# midiprog.net
KiCad netlist of a schematic drawn in EAGLE
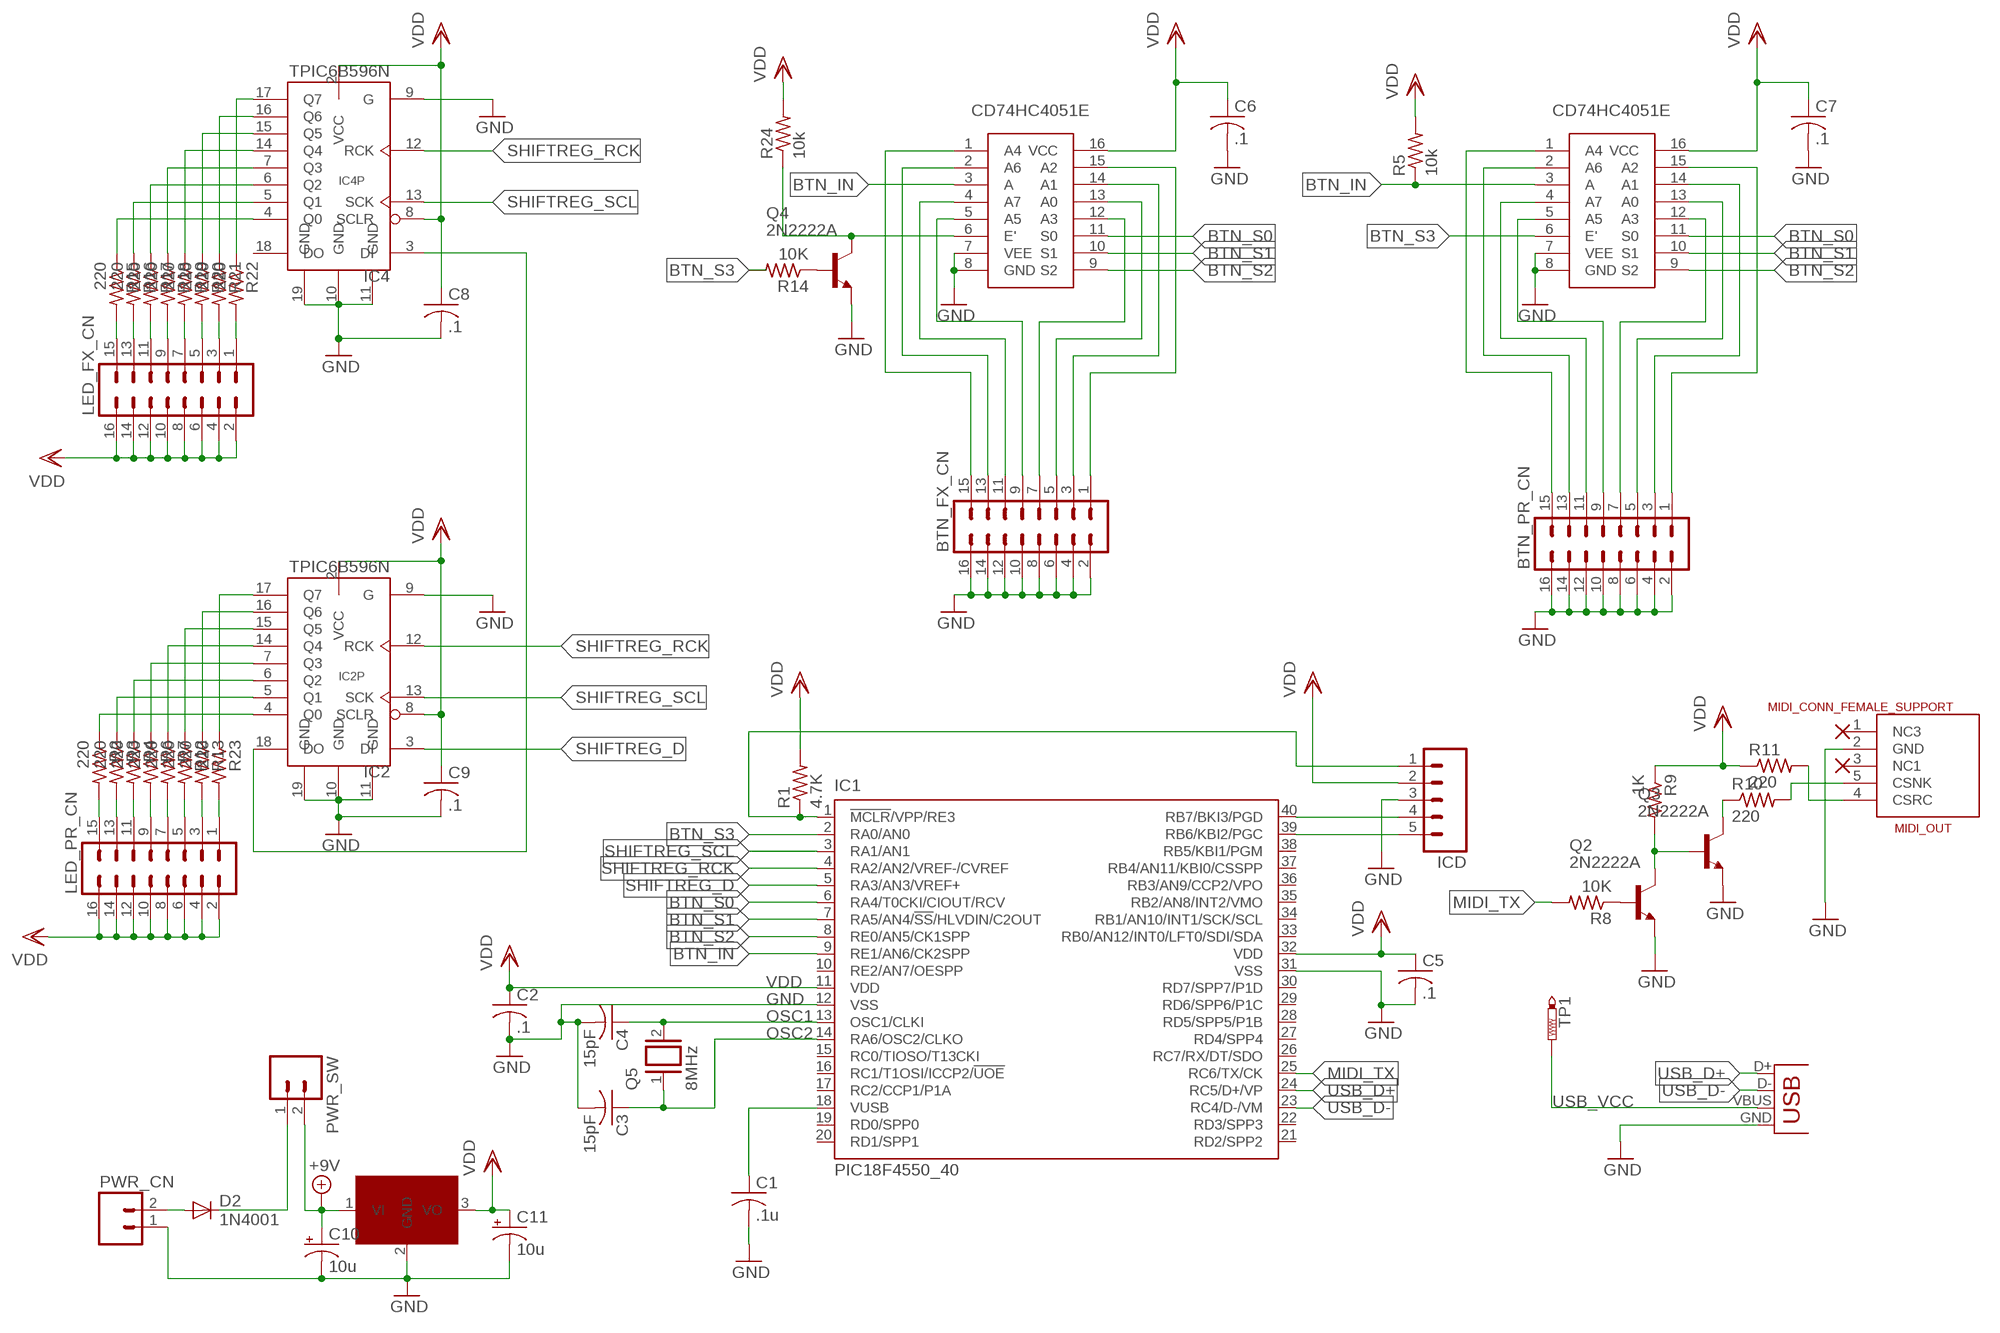
[diagram p0: schematic, sheet 1]

(export (version "E")
  (design (tool "Eeschema 10.0.6"))
  (components
    (comp (ref "BTN_FX_CN")
      (value "MA08-2")
      (footprint "eagle-import:MA08-2")
      (libsource (lib "eagle-import") (part "MA08-2"))
    )
    (comp (ref "BTN_PR_CN")
      (value "MA08-2")
      (footprint "eagle-import:MA08-2")
      (libsource (lib "eagle-import") (part "MA08-2"))
    )
    (comp (ref "C1")
      (value ".1u")
      (footprint "eagle-import:C050-025X075")
      (libsource (lib "eagle-import") (part "C-US050-025X075"))
    )
    (comp (ref "C2")
      (value ".1")
      (footprint "eagle-import:C050-025X075")
      (libsource (lib "eagle-import") (part "C-US050-025X075"))
    )
    (comp (ref "C3")
      (value "15pF")
      (footprint "eagle-import:C050-025X075")
      (libsource (lib "eagle-import") (part "C-US050-025X075"))
    )
    (comp (ref "C4")
      (value "15pF")
      (footprint "eagle-import:C050-025X075")
      (libsource (lib "eagle-import") (part "C-US050-025X075"))
    )
    (comp (ref "C5")
      (value ".1")
      (footprint "eagle-import:C050-025X075")
      (libsource (lib "eagle-import") (part "C-US050-025X075"))
    )
    (comp (ref "C6")
      (value ".1")
      (footprint "eagle-import:C050-025X075")
      (libsource (lib "eagle-import") (part "C-US050-025X075"))
    )
    (comp (ref "C7")
      (value ".1")
      (footprint "eagle-import:C050-025X075")
      (libsource (lib "eagle-import") (part "C-US050-025X075"))
    )
    (comp (ref "C8")
      (value ".1")
      (footprint "eagle-import:C050-025X075")
      (libsource (lib "eagle-import") (part "C-US050-025X075"))
    )
    (comp (ref "C9")
      (value ".1")
      (footprint "eagle-import:C050-025X075")
      (libsource (lib "eagle-import") (part "C-US050-025X075"))
    )
    (comp (ref "C10")
      (value "10u")
      (footprint "eagle-import:E2,5-6")
      (libsource (lib "eagle-import") (part "CPOL-USE2.5-6"))
    )
    (comp (ref "C11")
      (value "10u")
      (footprint "eagle-import:E2,5-6")
      (libsource (lib "eagle-import") (part "CPOL-USE2.5-6"))
    )
    (comp (ref "D2")
      (value "1N4001")
      (footprint "eagle-import:DO41-10")
      (libsource (lib "eagle-import") (part "1N4004"))
    )
    (comp (ref "IC1")
      (value "PIC18F4550_40")
      (footprint "eagle-import:DIL40")
      (fields (field (name "MF") "MICROCHIP") (field (name "MPN") "PIC18F4550-I/P"))
      (libsource (lib "eagle-import") (part "PIC18F4_40550"))
    )
    (comp (ref "IC2")
      (value "TPIC6B596N")
      (footprint "eagle-import:DIL20")
      (libsource (lib "eagle-import") (part "TPIC6B596N"))
    )
    (comp (ref "IC4")
      (value "TPIC6B596N")
      (footprint "eagle-import:DIL20")
      (libsource (lib "eagle-import") (part "TPIC6B596N"))
    )
    (comp (ref "ICD")
      (value "MA05")
      (footprint "eagle-import:05PA")
      (libsource (lib "eagle-import") (part "MA05"))
    )
    (comp (ref "JP1")
      (value "USB-B")
      (footprint "eagle-import:USB-B-PTH")
      (libsource (lib "eagle-import") (part "USBPTH"))
    )
    (comp (ref "LED_FX_CN")
      (value "MA08-2")
      (footprint "eagle-import:MA08-2")
      (libsource (lib "eagle-import") (part "MA08-2"))
    )
    (comp (ref "LED_PR_CN")
      (value "MA08-2")
      (footprint "eagle-import:MA08-2")
      (libsource (lib "eagle-import") (part "MA08-2"))
    )
    (comp (ref "MIDI_OUT")
      (value "MIDI_CONN_FEMALE_SUPPORT")
      (footprint "eagle-import:DIN_5_FEMALE_SUPPORT")
      (libsource (lib "eagle-import") (part "MIDI_CONN_FEMALE_SUPPORT"))
    )
    (comp (ref "PWR_CN")
      (value "M02")
      (footprint "eagle-import:02P")
      (libsource (lib "eagle-import") (part "M02"))
    )
    (comp (ref "PWR_SW")
      (value "M02")
      (footprint "eagle-import:02P")
      (libsource (lib "eagle-import") (part "M02"))
    )
    (comp (ref "Q2")
      (value "2N2222A")
      (footprint "eagle-import:TO18")
      (libsource (lib "eagle-import") (part "2N2222A"))
    )
    (comp (ref "Q3")
      (value "2N2222A")
      (footprint "eagle-import:TO18")
      (libsource (lib "eagle-import") (part "2N2222A"))
    )
    (comp (ref "Q4")
      (value "2N2222A")
      (footprint "eagle-import:TO18")
      (libsource (lib "eagle-import") (part "2N2222A"))
    )
    (comp (ref "Q5")
      (value "8MHz")
      (footprint "eagle-import:QS")
      (libsource (lib "eagle-import") (part "XTAL/S"))
    )
    (comp (ref "R1")
      (value "4.7K")
      (footprint "eagle-import:0207_10")
      (libsource (lib "eagle-import") (part "R-US_0207/10"))
    )
    (comp (ref "R2")
      (value "220")
      (footprint "eagle-import:0207_10")
      (libsource (lib "eagle-import") (part "R-US_0207/10"))
    )
    (comp (ref "R3")
      (value "220")
      (footprint "eagle-import:0207_10")
      (libsource (lib "eagle-import") (part "R-US_0207/10"))
    )
    (comp (ref "R4")
      (value "220")
      (footprint "eagle-import:0207_10")
      (libsource (lib "eagle-import") (part "R-US_0207/10"))
    )
    (comp (ref "R5")
      (value "10k")
      (footprint "eagle-import:0207_10")
      (libsource (lib "eagle-import") (part "R-US_0207/10"))
    )
    (comp (ref "R6")
      (value "220")
      (footprint "eagle-import:0207_10")
      (libsource (lib "eagle-import") (part "R-US_0207/10"))
    )
    (comp (ref "R7")
      (value "220")
      (footprint "eagle-import:0207_10")
      (libsource (lib "eagle-import") (part "R-US_0207/10"))
    )
    (comp (ref "R8")
      (value "10K")
      (footprint "eagle-import:0207_10")
      (libsource (lib "eagle-import") (part "R-US_0207/10"))
    )
    (comp (ref "R9")
      (value "1K")
      (footprint "eagle-import:0207_10")
      (libsource (lib "eagle-import") (part "R-US_0207/10"))
    )
    (comp (ref "R10")
      (value "220")
      (footprint "eagle-import:0207_10")
      (libsource (lib "eagle-import") (part "R-US_0207/10"))
    )
    (comp (ref "R11")
      (value "220")
      (footprint "eagle-import:0207_10")
      (libsource (lib "eagle-import") (part "R-US_0207/10"))
    )
    (comp (ref "R12")
      (value "220")
      (footprint "eagle-import:0207_10")
      (libsource (lib "eagle-import") (part "R-US_0207/10"))
    )
    (comp (ref "R13")
      (value "220")
      (footprint "eagle-import:0207_10")
      (libsource (lib "eagle-import") (part "R-US_0207/10"))
    )
    (comp (ref "R14")
      (value "10K")
      (footprint "eagle-import:0207_10")
      (libsource (lib "eagle-import") (part "R-US_0207/10"))
    )
    (comp (ref "R15")
      (value "220")
      (footprint "eagle-import:0207_10")
      (libsource (lib "eagle-import") (part "R-US_0207/10"))
    )
    (comp (ref "R16")
      (value "220")
      (footprint "eagle-import:0207_10")
      (libsource (lib "eagle-import") (part "R-US_0207/10"))
    )
    (comp (ref "R17")
      (value "220")
      (footprint "eagle-import:0207_10")
      (libsource (lib "eagle-import") (part "R-US_0207/10"))
    )
    (comp (ref "R18")
      (value "220")
      (footprint "eagle-import:0207_10")
      (libsource (lib "eagle-import") (part "R-US_0207/10"))
    )
    (comp (ref "R19")
      (value "220")
      (footprint "eagle-import:0207_10")
      (libsource (lib "eagle-import") (part "R-US_0207/10"))
    )
    (comp (ref "R20")
      (value "220")
      (footprint "eagle-import:0207_10")
      (libsource (lib "eagle-import") (part "R-US_0207/10"))
    )
    (comp (ref "R21")
      (value "220")
      (footprint "eagle-import:0207_10")
      (libsource (lib "eagle-import") (part "R-US_0207/10"))
    )
    (comp (ref "R22")
      (value "220")
      (footprint "eagle-import:0207_10")
      (libsource (lib "eagle-import") (part "R-US_0207/10"))
    )
    (comp (ref "R23")
      (value "220")
      (footprint "eagle-import:0207_10")
      (libsource (lib "eagle-import") (part "R-US_0207/10"))
    )
    (comp (ref "R24")
      (value "10k")
      (footprint "eagle-import:0207_10")
      (libsource (lib "eagle-import") (part "R-US_0207/10"))
    )
    (comp (ref "TP1")
      (value "PTR1PAD1-17")
      (footprint "eagle-import:P1-17")
      (libsource (lib "eagle-import") (part "PTR1PAD1-17"))
    )
    (comp (ref "U$1")
      (value "CD74HC4051E")
      (footprint "eagle-import:CD74HC4051E")
      (libsource (lib "eagle-import") (part "CD74HC4051E"))
    )
    (comp (ref "U$2")
      (value "CD74HC4051E")
      (footprint "eagle-import:CD74HC4051E")
      (libsource (lib "eagle-import") (part "CD74HC4051E"))
    )
    (comp (ref "U$3")
      (value "7805")
      (footprint "eagle-import:JKDFJD")
      (libsource (lib "eagle-import") (part "7805"))
    )
  )
  (nets
    (net (code "1") (name "+9V") (class "Default")
      (node (ref "C10") (pin "+") (pinfunction "+_+") (pintype "passive"))
      (node (ref "PWR_SW") (pin "2") (pinfunction "2_2") (pintype "passive"))
      (node (ref "U$3") (pin "1") (pinfunction "VI_1") (pintype "bidirectional"))
    )
    (net (code "2") (name "/OSC1") (class "Default")
      (node (ref "C4") (pin "1") (pinfunction "1_1") (pintype "passive"))
      (node (ref "IC1") (pin "13") (pinfunction "OSC1/CLKI_13") (pintype "input"))
      (node (ref "Q5") (pin "2") (pinfunction "2_2") (pintype "passive"))
    )
    (net (code "3") (name "/OSC2") (class "Default")
      (node (ref "C3") (pin "1") (pinfunction "1_1") (pintype "passive"))
      (node (ref "IC1") (pin "14") (pinfunction "RA6/OSC2/CLKO_14") (pintype "output"))
      (node (ref "Q5") (pin "1") (pinfunction "1_1") (pintype "passive"))
    )
    (net (code "4") (name "/USB_VCC") (class "Default")
      (node (ref "JP1") (pin "VBUS") (pinfunction "VBUS_VBUS") (pintype "bidirectional"))
      (node (ref "TP1") (pin "TP") (pinfunction "TP_TP") (pintype "input"))
    )
    (net (code "5") (name "BTN_IN") (class "Default")
      (node (ref "IC1") (pin "9") (pinfunction "RE1/AN6/CK2SPP_9") (pintype "bidirectional"))
      (node (ref "R5") (pin "1") (pinfunction "1_1") (pintype "passive"))
      (node (ref "U$1") (pin "3") (pinfunction "A_3") (pintype "bidirectional"))
      (node (ref "U$2") (pin "3") (pinfunction "A_3") (pintype "bidirectional"))
    )
    (net (code "6") (name "BTN_S0") (class "Default")
      (node (ref "IC1") (pin "6") (pinfunction "RA4/T0CKI/CIOUT/RCV_6") (pintype "bidirectional"))
      (node (ref "U$1") (pin "11") (pinfunction "S0_11") (pintype "bidirectional"))
      (node (ref "U$2") (pin "11") (pinfunction "S0_11") (pintype "bidirectional"))
    )
    (net (code "7") (name "BTN_S1") (class "Default")
      (node (ref "IC1") (pin "7") (pinfunction "RA5/AN4/~{SS}/HLVDIN/C2OUT_7") (pintype "bidirectional"))
      (node (ref "U$1") (pin "10") (pinfunction "S1_10") (pintype "bidirectional"))
      (node (ref "U$2") (pin "10") (pinfunction "S1_10") (pintype "bidirectional"))
    )
    (net (code "8") (name "BTN_S2") (class "Default")
      (node (ref "IC1") (pin "8") (pinfunction "RE0/AN5/CK1SPP_8") (pintype "bidirectional"))
      (node (ref "U$1") (pin "9") (pinfunction "S2_9") (pintype "bidirectional"))
      (node (ref "U$2") (pin "9") (pinfunction "S2_9") (pintype "bidirectional"))
    )
    (net (code "9") (name "BTN_S3") (class "Default")
      (node (ref "IC1") (pin "2") (pinfunction "RA0/AN0_2") (pintype "bidirectional"))
      (node (ref "R14") (pin "2") (pinfunction "2_2") (pintype "passive"))
      (node (ref "U$1") (pin "6") (pinfunction "E'_6") (pintype "bidirectional"))
    )
    (net (code "10") (name "GND") (class "Default")
      (node (ref "BTN_FX_CN") (pin "10") (pinfunction "10_10") (pintype "passive"))
      (node (ref "BTN_FX_CN") (pin "12") (pinfunction "12_12") (pintype "passive"))
      (node (ref "BTN_FX_CN") (pin "14") (pinfunction "14_14") (pintype "passive"))
      (node (ref "BTN_FX_CN") (pin "16") (pinfunction "16_16") (pintype "passive"))
      (node (ref "BTN_FX_CN") (pin "2") (pinfunction "2_2") (pintype "passive"))
      (node (ref "BTN_FX_CN") (pin "4") (pinfunction "4_4") (pintype "passive"))
      (node (ref "BTN_FX_CN") (pin "6") (pinfunction "6_6") (pintype "passive"))
      (node (ref "BTN_FX_CN") (pin "8") (pinfunction "8_8") (pintype "passive"))
      (node (ref "BTN_PR_CN") (pin "10") (pinfunction "10_10") (pintype "passive"))
      (node (ref "BTN_PR_CN") (pin "12") (pinfunction "12_12") (pintype "passive"))
      (node (ref "BTN_PR_CN") (pin "14") (pinfunction "14_14") (pintype "passive"))
      (node (ref "BTN_PR_CN") (pin "16") (pinfunction "16_16") (pintype "passive"))
      (node (ref "BTN_PR_CN") (pin "2") (pinfunction "2_2") (pintype "passive"))
      (node (ref "BTN_PR_CN") (pin "4") (pinfunction "4_4") (pintype "passive"))
      (node (ref "BTN_PR_CN") (pin "6") (pinfunction "6_6") (pintype "passive"))
      (node (ref "BTN_PR_CN") (pin "8") (pinfunction "8_8") (pintype "passive"))
      (node (ref "C1") (pin "2") (pinfunction "2_2") (pintype "passive"))
      (node (ref "C10") (pin "-") (pinfunction "-_-") (pintype "passive"))
      (node (ref "C11") (pin "-") (pinfunction "-_-") (pintype "passive"))
      (node (ref "C2") (pin "2") (pinfunction "2_2") (pintype "passive"))
      (node (ref "C3") (pin "2") (pinfunction "2_2") (pintype "passive"))
      (node (ref "C4") (pin "2") (pinfunction "2_2") (pintype "passive"))
      (node (ref "C5") (pin "2") (pinfunction "2_2") (pintype "passive"))
      (node (ref "C6") (pin "2") (pinfunction "2_2") (pintype "passive"))
      (node (ref "C7") (pin "2") (pinfunction "2_2") (pintype "passive"))
      (node (ref "C8") (pin "2") (pinfunction "2_2") (pintype "passive"))
      (node (ref "C9") (pin "2") (pinfunction "2_2") (pintype "passive"))
      (node (ref "IC1") (pin "12") (pinfunction "VSS_12") (pintype "power_in"))
      (node (ref "IC1") (pin "31") (pinfunction "VSS_31") (pintype "power_in"))
      (node (ref "IC2") (pin "10") (pinfunction "GND_10") (pintype "power_in"))
      (node (ref "IC2") (pin "11") (pinfunction "GND_11") (pintype "power_in"))
      (node (ref "IC2") (pin "19") (pinfunction "GND_19") (pintype "power_in"))
      (node (ref "IC2") (pin "9") (pinfunction "G_9") (pintype "input"))
      (node (ref "IC4") (pin "10") (pinfunction "GND_10") (pintype "power_in"))
      (node (ref "IC4") (pin "11") (pinfunction "GND_11") (pintype "power_in"))
      (node (ref "IC4") (pin "19") (pinfunction "GND_19") (pintype "power_in"))
      (node (ref "IC4") (pin "9") (pinfunction "G_9") (pintype "input"))
      (node (ref "ICD") (pin "3") (pinfunction "3_3") (pintype "passive"))
      (node (ref "JP1") (pin "GND") (pinfunction "GND_GND") (pintype "bidirectional"))
      (node (ref "MIDI_OUT") (pin "2") (pinfunction "GND_2") (pintype "bidirectional"))
      (node (ref "PWR_CN") (pin "1") (pinfunction "1_1") (pintype "passive"))
      (node (ref "Q2") (pin "1") (pinfunction "E_1") (pintype "passive"))
      (node (ref "Q3") (pin "1") (pinfunction "E_1") (pintype "passive"))
      (node (ref "Q4") (pin "1") (pinfunction "E_1") (pintype "passive"))
      (node (ref "U$1") (pin "7") (pinfunction "VEE_7") (pintype "bidirectional"))
      (node (ref "U$1") (pin "8") (pinfunction "GND_8") (pintype "bidirectional"))
      (node (ref "U$2") (pin "7") (pinfunction "VEE_7") (pintype "bidirectional"))
      (node (ref "U$2") (pin "8") (pinfunction "GND_8") (pintype "bidirectional"))
      (node (ref "U$3") (pin "2") (pinfunction "GND_2") (pintype "bidirectional"))
    )
    (net (code "11") (name "MIDI_TX") (class "Default")
      (node (ref "IC1") (pin "25") (pinfunction "RC6/TX/CK_25") (pintype "bidirectional"))
      (node (ref "R8") (pin "2") (pinfunction "2_2") (pintype "passive"))
    )
    (net (code "12") (name "Net-(D2-PadA)") (class "Default")
      (node (ref "D2") (pin "A") (pinfunction "A_A") (pintype "passive"))
      (node (ref "PWR_CN") (pin "2") (pinfunction "2_2") (pintype "passive"))
    )
    (net (code "13") (name "Net-(D2-PadC)") (class "Default")
      (node (ref "D2") (pin "C") (pinfunction "C_C") (pintype "passive"))
      (node (ref "PWR_SW") (pin "1") (pinfunction "1_1") (pintype "passive"))
    )
    (net (code "14") (name "Net-(IC1-RB6{slash}KBI2{slash}PGC)") (class "Default")
      (node (ref "IC1") (pin "39") (pinfunction "RB6/KBI2/PGC_39") (pintype "bidirectional"))
      (node (ref "ICD") (pin "5") (pinfunction "5_5") (pintype "passive"))
    )
    (net (code "15") (name "Net-(IC1-RB7{slash}BKI3{slash}PGD)") (class "Default")
      (node (ref "IC1") (pin "40") (pinfunction "RB7/BKI3/PGD_40") (pintype "bidirectional"))
      (node (ref "ICD") (pin "4") (pinfunction "4_4") (pintype "passive"))
    )
    (net (code "16") (name "Net-(IC1-VUSB)") (class "Default")
      (node (ref "C1") (pin "1") (pinfunction "1_1") (pintype "passive"))
      (node (ref "IC1") (pin "18") (pinfunction "VUSB_18") (pintype "bidirectional"))
    )
    (net (code "17") (name "Net-(IC1-~{MCLR}{slash}VPP{slash}RE3)") (class "Default")
      (node (ref "IC1") (pin "1") (pinfunction "~{MCLR}/VPP/RE3_1") (pintype "input"))
      (node (ref "ICD") (pin "1") (pinfunction "1_1") (pintype "passive"))
      (node (ref "R1") (pin "1") (pinfunction "1_1") (pintype "passive"))
    )
    (net (code "18") (name "Net-(IC2A-DO)") (class "Default")
      (node (ref "IC2") (pin "18") (pinfunction "DO_18") (pintype "output"))
      (node (ref "IC4") (pin "3") (pinfunction "DI_3") (pintype "input"))
    )
    (net (code "19") (name "Net-(IC2A-Q0)") (class "Default")
      (node (ref "IC2") (pin "4") (pinfunction "Q0_4") (pintype "open_collector"))
      (node (ref "R2") (pin "1") (pinfunction "1_1") (pintype "passive"))
    )
    (net (code "20") (name "Net-(IC2A-Q1)") (class "Default")
      (node (ref "IC2") (pin "5") (pinfunction "Q1_5") (pintype "open_collector"))
      (node (ref "R3") (pin "1") (pinfunction "1_1") (pintype "passive"))
    )
    (net (code "21") (name "Net-(IC2A-Q2)") (class "Default")
      (node (ref "IC2") (pin "6") (pinfunction "Q2_6") (pintype "open_collector"))
      (node (ref "R4") (pin "1") (pinfunction "1_1") (pintype "passive"))
    )
    (net (code "22") (name "Net-(IC2A-Q3)") (class "Default")
      (node (ref "IC2") (pin "7") (pinfunction "Q3_7") (pintype "open_collector"))
      (node (ref "R6") (pin "1") (pinfunction "1_1") (pintype "passive"))
    )
    (net (code "23") (name "Net-(IC2A-Q4)") (class "Default")
      (node (ref "IC2") (pin "14") (pinfunction "Q4_14") (pintype "open_collector"))
      (node (ref "R7") (pin "1") (pinfunction "1_1") (pintype "passive"))
    )
    (net (code "24") (name "Net-(IC2A-Q5)") (class "Default")
      (node (ref "IC2") (pin "15") (pinfunction "Q5_15") (pintype "open_collector"))
      (node (ref "R12") (pin "1") (pinfunction "1_1") (pintype "passive"))
    )
    (net (code "25") (name "Net-(IC2A-Q6)") (class "Default")
      (node (ref "IC2") (pin "16") (pinfunction "Q6_16") (pintype "open_collector"))
      (node (ref "R13") (pin "1") (pinfunction "1_1") (pintype "passive"))
    )
    (net (code "26") (name "Net-(IC2A-Q7)") (class "Default")
      (node (ref "IC2") (pin "17") (pinfunction "Q7_17") (pintype "open_collector"))
      (node (ref "R23") (pin "1") (pinfunction "1_1") (pintype "passive"))
    )
    (net (code "27") (name "Net-(IC4A-Q0)") (class "Default")
      (node (ref "IC4") (pin "4") (pinfunction "Q0_4") (pintype "open_collector"))
      (node (ref "R15") (pin "1") (pinfunction "1_1") (pintype "passive"))
    )
    (net (code "28") (name "Net-(IC4A-Q1)") (class "Default")
      (node (ref "IC4") (pin "5") (pinfunction "Q1_5") (pintype "open_collector"))
      (node (ref "R16") (pin "1") (pinfunction "1_1") (pintype "passive"))
    )
    (net (code "29") (name "Net-(IC4A-Q2)") (class "Default")
      (node (ref "IC4") (pin "6") (pinfunction "Q2_6") (pintype "open_collector"))
      (node (ref "R17") (pin "1") (pinfunction "1_1") (pintype "passive"))
    )
    (net (code "30") (name "Net-(IC4A-Q3)") (class "Default")
      (node (ref "IC4") (pin "7") (pinfunction "Q3_7") (pintype "open_collector"))
      (node (ref "R18") (pin "1") (pinfunction "1_1") (pintype "passive"))
    )
    (net (code "31") (name "Net-(IC4A-Q4)") (class "Default")
      (node (ref "IC4") (pin "14") (pinfunction "Q4_14") (pintype "open_collector"))
      (node (ref "R19") (pin "1") (pinfunction "1_1") (pintype "passive"))
    )
    (net (code "32") (name "Net-(IC4A-Q5)") (class "Default")
      (node (ref "IC4") (pin "15") (pinfunction "Q5_15") (pintype "open_collector"))
      (node (ref "R20") (pin "1") (pinfunction "1_1") (pintype "passive"))
    )
    (net (code "33") (name "Net-(IC4A-Q6)") (class "Default")
      (node (ref "IC4") (pin "16") (pinfunction "Q6_16") (pintype "open_collector"))
      (node (ref "R21") (pin "1") (pinfunction "1_1") (pintype "passive"))
    )
    (net (code "34") (name "Net-(IC4A-Q7)") (class "Default")
      (node (ref "IC4") (pin "17") (pinfunction "Q7_17") (pintype "open_collector"))
      (node (ref "R22") (pin "1") (pinfunction "1_1") (pintype "passive"))
    )
    (net (code "35") (name "Net-(LED_FX_CN-Pad1)") (class "Default")
      (node (ref "LED_FX_CN") (pin "1") (pinfunction "1_1") (pintype "passive"))
      (node (ref "R22") (pin "2") (pinfunction "2_2") (pintype "passive"))
    )
    (net (code "36") (name "Net-(LED_FX_CN-Pad3)") (class "Default")
      (node (ref "LED_FX_CN") (pin "3") (pinfunction "3_3") (pintype "passive"))
      (node (ref "R21") (pin "2") (pinfunction "2_2") (pintype "passive"))
    )
    (net (code "37") (name "Net-(LED_FX_CN-Pad5)") (class "Default")
      (node (ref "LED_FX_CN") (pin "5") (pinfunction "5_5") (pintype "passive"))
      (node (ref "R20") (pin "2") (pinfunction "2_2") (pintype "passive"))
    )
    (net (code "38") (name "Net-(LED_FX_CN-Pad7)") (class "Default")
      (node (ref "LED_FX_CN") (pin "7") (pinfunction "7_7") (pintype "passive"))
      (node (ref "R19") (pin "2") (pinfunction "2_2") (pintype "passive"))
    )
    (net (code "39") (name "Net-(LED_FX_CN-Pad9)") (class "Default")
      (node (ref "LED_FX_CN") (pin "9") (pinfunction "9_9") (pintype "passive"))
      (node (ref "R18") (pin "2") (pinfunction "2_2") (pintype "passive"))
    )
    (net (code "40") (name "Net-(LED_FX_CN-Pad11)") (class "Default")
      (node (ref "LED_FX_CN") (pin "11") (pinfunction "11_11") (pintype "passive"))
      (node (ref "R17") (pin "2") (pinfunction "2_2") (pintype "passive"))
    )
    (net (code "41") (name "Net-(LED_FX_CN-Pad13)") (class "Default")
      (node (ref "LED_FX_CN") (pin "13") (pinfunction "13_13") (pintype "passive"))
      (node (ref "R16") (pin "2") (pinfunction "2_2") (pintype "passive"))
    )
    (net (code "42") (name "Net-(LED_FX_CN-Pad15)") (class "Default")
      (node (ref "LED_FX_CN") (pin "15") (pinfunction "15_15") (pintype "passive"))
      (node (ref "R15") (pin "2") (pinfunction "2_2") (pintype "passive"))
    )
    (net (code "43") (name "Net-(LED_PR_CN-Pad1)") (class "Default")
      (node (ref "LED_PR_CN") (pin "1") (pinfunction "1_1") (pintype "passive"))
      (node (ref "R23") (pin "2") (pinfunction "2_2") (pintype "passive"))
    )
    (net (code "44") (name "Net-(LED_PR_CN-Pad3)") (class "Default")
      (node (ref "LED_PR_CN") (pin "3") (pinfunction "3_3") (pintype "passive"))
      (node (ref "R13") (pin "2") (pinfunction "2_2") (pintype "passive"))
    )
    (net (code "45") (name "Net-(LED_PR_CN-Pad5)") (class "Default")
      (node (ref "LED_PR_CN") (pin "5") (pinfunction "5_5") (pintype "passive"))
      (node (ref "R12") (pin "2") (pinfunction "2_2") (pintype "passive"))
    )
    (net (code "46") (name "Net-(LED_PR_CN-Pad7)") (class "Default")
      (node (ref "LED_PR_CN") (pin "7") (pinfunction "7_7") (pintype "passive"))
      (node (ref "R7") (pin "2") (pinfunction "2_2") (pintype "passive"))
    )
    (net (code "47") (name "Net-(LED_PR_CN-Pad9)") (class "Default")
      (node (ref "LED_PR_CN") (pin "9") (pinfunction "9_9") (pintype "passive"))
      (node (ref "R6") (pin "2") (pinfunction "2_2") (pintype "passive"))
    )
    (net (code "48") (name "Net-(LED_PR_CN-Pad11)") (class "Default")
      (node (ref "LED_PR_CN") (pin "11") (pinfunction "11_11") (pintype "passive"))
      (node (ref "R4") (pin "2") (pinfunction "2_2") (pintype "passive"))
    )
    (net (code "49") (name "Net-(LED_PR_CN-Pad13)") (class "Default")
      (node (ref "LED_PR_CN") (pin "13") (pinfunction "13_13") (pintype "passive"))
      (node (ref "R3") (pin "2") (pinfunction "2_2") (pintype "passive"))
    )
    (net (code "50") (name "Net-(LED_PR_CN-Pad15)") (class "Default")
      (node (ref "LED_PR_CN") (pin "15") (pinfunction "15_15") (pintype "passive"))
      (node (ref "R2") (pin "2") (pinfunction "2_2") (pintype "passive"))
    )
    (net (code "51") (name "Net-(MIDI_OUT-CSNK)") (class "Default")
      (node (ref "MIDI_OUT") (pin "5") (pinfunction "CSNK_5") (pintype "bidirectional"))
      (node (ref "R10") (pin "2") (pinfunction "2_2") (pintype "passive"))
    )
    (net (code "52") (name "Net-(MIDI_OUT-CSRC)") (class "Default")
      (node (ref "MIDI_OUT") (pin "4") (pinfunction "CSRC_4") (pintype "bidirectional"))
      (node (ref "R11") (pin "2") (pinfunction "2_2") (pintype "passive"))
    )
    (net (code "53") (name "Net-(Q2-B)") (class "Default")
      (node (ref "Q2") (pin "2") (pinfunction "B_2") (pintype "passive"))
      (node (ref "R8") (pin "1") (pinfunction "1_1") (pintype "passive"))
    )
    (net (code "54") (name "Net-(Q2-C)") (class "Default")
      (node (ref "Q2") (pin "3") (pinfunction "C_3") (pintype "passive"))
      (node (ref "Q3") (pin "2") (pinfunction "B_2") (pintype "passive"))
      (node (ref "R9") (pin "2") (pinfunction "2_2") (pintype "passive"))
    )
    (net (code "55") (name "Net-(Q3-C)") (class "Default")
      (node (ref "Q3") (pin "3") (pinfunction "C_3") (pintype "passive"))
      (node (ref "R10") (pin "1") (pinfunction "1_1") (pintype "passive"))
    )
    (net (code "56") (name "Net-(Q4-B)") (class "Default")
      (node (ref "Q4") (pin "2") (pinfunction "B_2") (pintype "passive"))
      (node (ref "R14") (pin "1") (pinfunction "1_1") (pintype "passive"))
    )
    (net (code "57") (name "Net-(Q4-C)") (class "Default")
      (node (ref "Q4") (pin "3") (pinfunction "C_3") (pintype "passive"))
      (node (ref "R24") (pin "1") (pinfunction "1_1") (pintype "passive"))
      (node (ref "U$2") (pin "6") (pinfunction "E'_6") (pintype "bidirectional"))
    )
    (net (code "58") (name "Net-(U$1-A0)") (class "Default")
      (node (ref "BTN_PR_CN") (pin "5") (pinfunction "5_5") (pintype "passive"))
      (node (ref "U$1") (pin "13") (pinfunction "A0_13") (pintype "bidirectional"))
    )
    (net (code "59") (name "Net-(U$1-A1)") (class "Default")
      (node (ref "BTN_PR_CN") (pin "3") (pinfunction "3_3") (pintype "passive"))
      (node (ref "U$1") (pin "14") (pinfunction "A1_14") (pintype "bidirectional"))
    )
    (net (code "60") (name "Net-(U$1-A2)") (class "Default")
      (node (ref "BTN_PR_CN") (pin "1") (pinfunction "1_1") (pintype "passive"))
      (node (ref "U$1") (pin "15") (pinfunction "A2_15") (pintype "bidirectional"))
    )
    (net (code "61") (name "Net-(U$1-A3)") (class "Default")
      (node (ref "BTN_PR_CN") (pin "7") (pinfunction "7_7") (pintype "passive"))
      (node (ref "U$1") (pin "12") (pinfunction "A3_12") (pintype "bidirectional"))
    )
    (net (code "62") (name "Net-(U$1-A4)") (class "Default")
      (node (ref "BTN_PR_CN") (pin "15") (pinfunction "15_15") (pintype "passive"))
      (node (ref "U$1") (pin "1") (pinfunction "A4_1") (pintype "bidirectional"))
    )
    (net (code "63") (name "Net-(U$1-A5)") (class "Default")
      (node (ref "BTN_PR_CN") (pin "9") (pinfunction "9_9") (pintype "passive"))
      (node (ref "U$1") (pin "5") (pinfunction "A5_5") (pintype "bidirectional"))
    )
    (net (code "64") (name "Net-(U$1-A6)") (class "Default")
      (node (ref "BTN_PR_CN") (pin "13") (pinfunction "13_13") (pintype "passive"))
      (node (ref "U$1") (pin "2") (pinfunction "A6_2") (pintype "bidirectional"))
    )
    (net (code "65") (name "Net-(U$1-A7)") (class "Default")
      (node (ref "BTN_PR_CN") (pin "11") (pinfunction "11_11") (pintype "passive"))
      (node (ref "U$1") (pin "4") (pinfunction "A7_4") (pintype "bidirectional"))
    )
    (net (code "66") (name "Net-(U$2-A0)") (class "Default")
      (node (ref "BTN_FX_CN") (pin "5") (pinfunction "5_5") (pintype "passive"))
      (node (ref "U$2") (pin "13") (pinfunction "A0_13") (pintype "bidirectional"))
    )
    (net (code "67") (name "Net-(U$2-A1)") (class "Default")
      (node (ref "BTN_FX_CN") (pin "3") (pinfunction "3_3") (pintype "passive"))
      (node (ref "U$2") (pin "14") (pinfunction "A1_14") (pintype "bidirectional"))
    )
    (net (code "68") (name "Net-(U$2-A2)") (class "Default")
      (node (ref "BTN_FX_CN") (pin "1") (pinfunction "1_1") (pintype "passive"))
      (node (ref "U$2") (pin "15") (pinfunction "A2_15") (pintype "bidirectional"))
    )
    (net (code "69") (name "Net-(U$2-A3)") (class "Default")
      (node (ref "BTN_FX_CN") (pin "7") (pinfunction "7_7") (pintype "passive"))
      (node (ref "U$2") (pin "12") (pinfunction "A3_12") (pintype "bidirectional"))
    )
    (net (code "70") (name "Net-(U$2-A4)") (class "Default")
      (node (ref "BTN_FX_CN") (pin "15") (pinfunction "15_15") (pintype "passive"))
      (node (ref "U$2") (pin "1") (pinfunction "A4_1") (pintype "bidirectional"))
    )
    (net (code "71") (name "Net-(U$2-A5)") (class "Default")
      (node (ref "BTN_FX_CN") (pin "9") (pinfunction "9_9") (pintype "passive"))
      (node (ref "U$2") (pin "5") (pinfunction "A5_5") (pintype "bidirectional"))
    )
    (net (code "72") (name "Net-(U$2-A6)") (class "Default")
      (node (ref "BTN_FX_CN") (pin "13") (pinfunction "13_13") (pintype "passive"))
      (node (ref "U$2") (pin "2") (pinfunction "A6_2") (pintype "bidirectional"))
    )
    (net (code "73") (name "Net-(U$2-A7)") (class "Default")
      (node (ref "BTN_FX_CN") (pin "11") (pinfunction "11_11") (pintype "passive"))
      (node (ref "U$2") (pin "4") (pinfunction "A7_4") (pintype "bidirectional"))
    )
    (net (code "74") (name "SHIFTREG_D") (class "Default")
      (node (ref "IC1") (pin "5") (pinfunction "RA3/AN3/VREF+_5") (pintype "bidirectional"))
      (node (ref "IC2") (pin "3") (pinfunction "DI_3") (pintype "input"))
    )
    (net (code "75") (name "SHIFTREG_RCK") (class "Default")
      (node (ref "IC1") (pin "4") (pinfunction "RA2/AN2/VREF-/CVREF_4") (pintype "bidirectional"))
      (node (ref "IC2") (pin "12") (pinfunction "RCK_12") (pintype "input"))
      (node (ref "IC4") (pin "12") (pinfunction "RCK_12") (pintype "input"))
    )
    (net (code "76") (name "SHIFTREG_SCL") (class "Default")
      (node (ref "IC1") (pin "3") (pinfunction "RA1/AN1_3") (pintype "bidirectional"))
      (node (ref "IC2") (pin "13") (pinfunction "SCK_13") (pintype "input"))
      (node (ref "IC4") (pin "13") (pinfunction "SCK_13") (pintype "input"))
    )
    (net (code "77") (name "USB_D+") (class "Default")
      (node (ref "IC1") (pin "24") (pinfunction "RC5/D+/VP_24") (pintype "bidirectional"))
      (node (ref "JP1") (pin "D+") (pinfunction "D+_D+") (pintype "bidirectional"))
    )
    (net (code "78") (name "USB_D-") (class "Default")
      (node (ref "IC1") (pin "23") (pinfunction "RC4/D-/VM_23") (pintype "bidirectional"))
      (node (ref "JP1") (pin "D-") (pinfunction "D-_D-") (pintype "bidirectional"))
    )
    (net (code "79") (name "VDD") (class "Default")
      (node (ref "C11") (pin "+") (pinfunction "+_+") (pintype "passive"))
      (node (ref "C2") (pin "1") (pinfunction "1_1") (pintype "passive"))
      (node (ref "C5") (pin "1") (pinfunction "1_1") (pintype "passive"))
      (node (ref "C6") (pin "1") (pinfunction "1_1") (pintype "passive"))
      (node (ref "C7") (pin "1") (pinfunction "1_1") (pintype "passive"))
      (node (ref "C8") (pin "1") (pinfunction "1_1") (pintype "passive"))
      (node (ref "C9") (pin "1") (pinfunction "1_1") (pintype "passive"))
      (node (ref "IC1") (pin "11") (pinfunction "VDD_11") (pintype "power_in"))
      (node (ref "IC1") (pin "32") (pinfunction "VDD_32") (pintype "power_in"))
      (node (ref "IC2") (pin "2") (pinfunction "VCC_2") (pintype "power_in"))
      (node (ref "IC2") (pin "8") (pinfunction "SCLR_8") (pintype "input"))
      (node (ref "IC4") (pin "2") (pinfunction "VCC_2") (pintype "power_in"))
      (node (ref "IC4") (pin "8") (pinfunction "SCLR_8") (pintype "input"))
      (node (ref "ICD") (pin "2") (pinfunction "2_2") (pintype "passive"))
      (node (ref "LED_FX_CN") (pin "10") (pinfunction "10_10") (pintype "passive"))
      (node (ref "LED_FX_CN") (pin "12") (pinfunction "12_12") (pintype "passive"))
      (node (ref "LED_FX_CN") (pin "14") (pinfunction "14_14") (pintype "passive"))
      (node (ref "LED_FX_CN") (pin "16") (pinfunction "16_16") (pintype "passive"))
      (node (ref "LED_FX_CN") (pin "2") (pinfunction "2_2") (pintype "passive"))
      (node (ref "LED_FX_CN") (pin "4") (pinfunction "4_4") (pintype "passive"))
      (node (ref "LED_FX_CN") (pin "6") (pinfunction "6_6") (pintype "passive"))
      (node (ref "LED_FX_CN") (pin "8") (pinfunction "8_8") (pintype "passive"))
      (node (ref "LED_PR_CN") (pin "10") (pinfunction "10_10") (pintype "passive"))
      (node (ref "LED_PR_CN") (pin "12") (pinfunction "12_12") (pintype "passive"))
      (node (ref "LED_PR_CN") (pin "14") (pinfunction "14_14") (pintype "passive"))
      (node (ref "LED_PR_CN") (pin "16") (pinfunction "16_16") (pintype "passive"))
      (node (ref "LED_PR_CN") (pin "2") (pinfunction "2_2") (pintype "passive"))
      (node (ref "LED_PR_CN") (pin "4") (pinfunction "4_4") (pintype "passive"))
      (node (ref "LED_PR_CN") (pin "6") (pinfunction "6_6") (pintype "passive"))
      (node (ref "LED_PR_CN") (pin "8") (pinfunction "8_8") (pintype "passive"))
      (node (ref "R1") (pin "2") (pinfunction "2_2") (pintype "passive"))
      (node (ref "R11") (pin "1") (pinfunction "1_1") (pintype "passive"))
      (node (ref "R24") (pin "2") (pinfunction "2_2") (pintype "passive"))
      (node (ref "R5") (pin "2") (pinfunction "2_2") (pintype "passive"))
      (node (ref "R9") (pin "1") (pinfunction "1_1") (pintype "passive"))
      (node (ref "U$1") (pin "16") (pinfunction "VCC_16") (pintype "bidirectional"))
      (node (ref "U$2") (pin "16") (pinfunction "VCC_16") (pintype "bidirectional"))
      (node (ref "U$3") (pin "3") (pinfunction "VO_3") (pintype "bidirectional"))
    )
    (net (code "80") (name "unconnected-(IC1-RB0{slash}AN12{slash}INT0{slash}LFT0{slash}SDI{slash}SDA-Pad33)") (class "Default")
      (node (ref "IC1") (pin "33") (pinfunction "RB0/AN12/INT0/LFT0/SDI/SDA_33") (pintype "bidirectional"))
    )
    (net (code "81") (name "unconnected-(IC1-RB1{slash}AN10{slash}INT1{slash}SCK{slash}SCL-Pad34)") (class "Default")
      (node (ref "IC1") (pin "34") (pinfunction "RB1/AN10/INT1/SCK/SCL_34") (pintype "bidirectional"))
    )
    (net (code "82") (name "unconnected-(IC1-RB2{slash}AN8{slash}INT2{slash}VMO-Pad35)") (class "Default")
      (node (ref "IC1") (pin "35") (pinfunction "RB2/AN8/INT2/VMO_35") (pintype "bidirectional"))
    )
    (net (code "83") (name "unconnected-(IC1-RB3{slash}AN9{slash}CCP2{slash}VPO-Pad36)") (class "Default")
      (node (ref "IC1") (pin "36") (pinfunction "RB3/AN9/CCP2/VPO_36") (pintype "bidirectional"))
    )
    (net (code "84") (name "unconnected-(IC1-RB4{slash}AN11{slash}KBI0{slash}CSSPP-Pad37)") (class "Default")
      (node (ref "IC1") (pin "37") (pinfunction "RB4/AN11/KBI0/CSSPP_37") (pintype "bidirectional"))
    )
    (net (code "85") (name "unconnected-(IC1-RB5{slash}KBI1{slash}PGM-Pad38)") (class "Default")
      (node (ref "IC1") (pin "38") (pinfunction "RB5/KBI1/PGM_38") (pintype "bidirectional"))
    )
    (net (code "86") (name "unconnected-(IC1-RC0{slash}TIOSO{slash}T13CKI-Pad15)") (class "Default")
      (node (ref "IC1") (pin "15") (pinfunction "RC0/TIOSO/T13CKI_15") (pintype "bidirectional"))
    )
    (net (code "87") (name "unconnected-(IC1-RC1{slash}T1OSI{slash}ICCP2{slash}~{UOE}-Pad16)") (class "Default")
      (node (ref "IC1") (pin "16") (pinfunction "RC1/T1OSI/ICCP2/~{UOE}_16") (pintype "bidirectional"))
    )
    (net (code "88") (name "unconnected-(IC1-RC2{slash}CCP1{slash}P1A-Pad17)") (class "Default")
      (node (ref "IC1") (pin "17") (pinfunction "RC2/CCP1/P1A_17") (pintype "bidirectional"))
    )
    (net (code "89") (name "unconnected-(IC1-RC7{slash}RX{slash}DT{slash}SDO-Pad26)") (class "Default")
      (node (ref "IC1") (pin "26") (pinfunction "RC7/RX/DT/SDO_26") (pintype "bidirectional"))
    )
    (net (code "90") (name "unconnected-(IC1-RD0{slash}SPP0-Pad19)") (class "Default")
      (node (ref "IC1") (pin "19") (pinfunction "RD0/SPP0_19") (pintype "bidirectional"))
    )
    (net (code "91") (name "unconnected-(IC1-RD1{slash}SPP1-Pad20)") (class "Default")
      (node (ref "IC1") (pin "20") (pinfunction "RD1/SPP1_20") (pintype "bidirectional"))
    )
    (net (code "92") (name "unconnected-(IC1-RD2{slash}SPP2-Pad21)") (class "Default")
      (node (ref "IC1") (pin "21") (pinfunction "RD2/SPP2_21") (pintype "bidirectional"))
    )
    (net (code "93") (name "unconnected-(IC1-RD3{slash}SPP3-Pad22)") (class "Default")
      (node (ref "IC1") (pin "22") (pinfunction "RD3/SPP3_22") (pintype "bidirectional"))
    )
    (net (code "94") (name "unconnected-(IC1-RD4{slash}SPP4-Pad27)") (class "Default")
      (node (ref "IC1") (pin "27") (pinfunction "RD4/SPP4_27") (pintype "bidirectional"))
    )
    (net (code "95") (name "unconnected-(IC1-RD5{slash}SPP5{slash}P1B-Pad28)") (class "Default")
      (node (ref "IC1") (pin "28") (pinfunction "RD5/SPP5/P1B_28") (pintype "bidirectional"))
    )
    (net (code "96") (name "unconnected-(IC1-RD6{slash}SPP6{slash}P1C-Pad29)") (class "Default")
      (node (ref "IC1") (pin "29") (pinfunction "RD6/SPP6/P1C_29") (pintype "bidirectional"))
    )
    (net (code "97") (name "unconnected-(IC1-RD7{slash}SPP7{slash}P1D-Pad30)") (class "Default")
      (node (ref "IC1") (pin "30") (pinfunction "RD7/SPP7/P1D_30") (pintype "bidirectional"))
    )
    (net (code "98") (name "unconnected-(IC1-RE2{slash}AN7{slash}OESPP-Pad10)") (class "Default")
      (node (ref "IC1") (pin "10") (pinfunction "RE2/AN7/OESPP_10") (pintype "bidirectional"))
    )
    (net (code "99") (name "unconnected-(IC4A-DO-Pad18)") (class "Default")
      (node (ref "IC4") (pin "18") (pinfunction "DO_18") (pintype "output"))
    )
    (net (code "100") (name "unconnected-(MIDI_OUT-NC1-Pad3)") (class "Default")
      (node (ref "MIDI_OUT") (pin "3") (pinfunction "NC1_3") (pintype "bidirectional"))
    )
    (net (code "101") (name "unconnected-(MIDI_OUT-NC3-Pad1)") (class "Default")
      (node (ref "MIDI_OUT") (pin "1") (pinfunction "NC3_1") (pintype "bidirectional"))
    )
  )
)
